# HIM-Otte-server-slow-control-V1-3.net
KiCad netlist of a schematic drawn in EAGLE
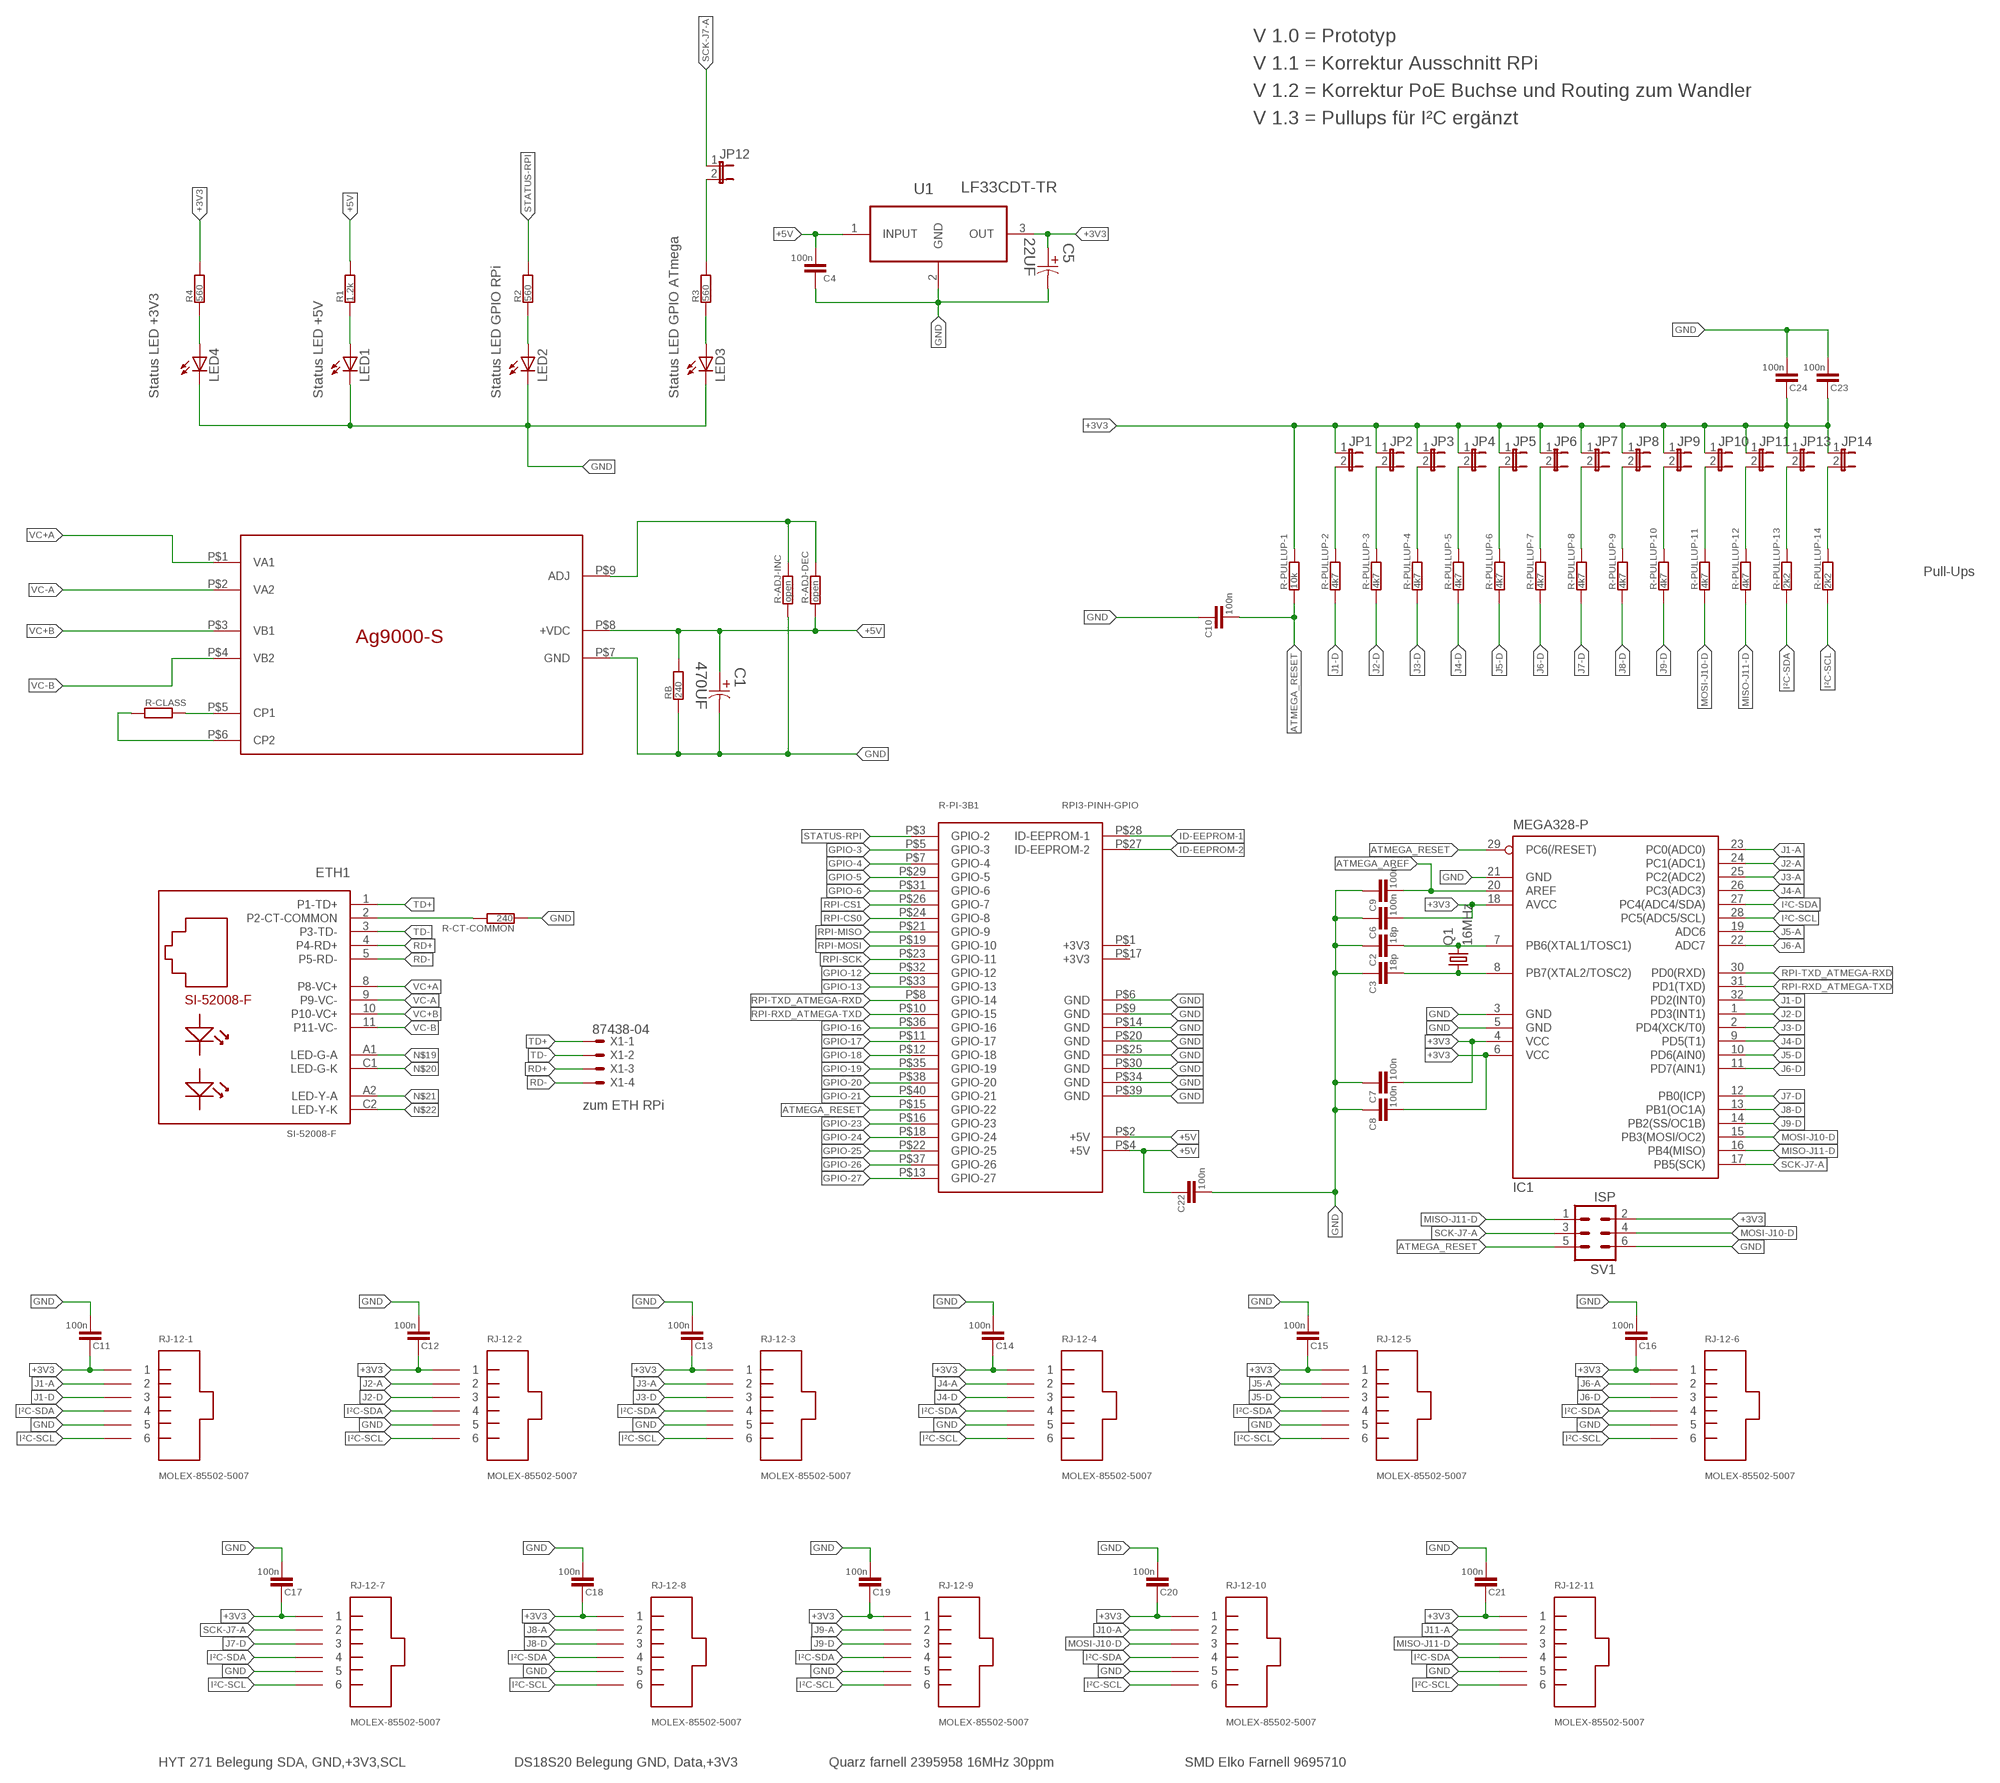
[diagram p0: schematic, sheet 1]

(export (version "E")
  (design (tool "Eeschema 10.0.6"))
  (components
    (comp (ref "C1")
      (value "470UF")
      (footprint "eagle-import:CAPAE830X1050N")
      (fields (field (name "MPN") "EEE-FK1C471P") (field (name "TOLERANCE") "±20 %"))
      (libsource (lib "eagle-import") (part "Panasonic-EEEFK_EEEFP_EEE--CASE-FFK1C471P"))
    )
    (comp (ref "C2")
      (value "18p")
      (footprint "eagle-import:C0603")
      (fields (field (name "TOLERANCE") "10%") (field (name "VOLTAGE") "16V"))
      (libsource (lib "eagle-import") (part "C-EUC0603"))
    )
    (comp (ref "C3")
      (value "18p")
      (footprint "eagle-import:C0603")
      (fields (field (name "TOLERANCE") "10%") (field (name "VOLTAGE") "16V"))
      (libsource (lib "eagle-import") (part "C-EUC0603"))
    )
    (comp (ref "C4")
      (value "100n")
      (footprint "eagle-import:C0603")
      (fields (field (name "TOLERANCE") "10%") (field (name "VOLTAGE") "16V"))
      (libsource (lib "eagle-import") (part "C-EUC0603"))
    )
    (comp (ref "C5")
      (value "22UF")
      (footprint "eagle-import:CAPAE530X610N")
      (fields (field (name "MPN") "EEE-FK1V220AR") (field (name "TOLERANCE") "±20 %"))
      (libsource (lib "eagle-import") (part "EEE--CASE-CFK1V220AR"))
    )
    (comp (ref "C6")
      (value "100n")
      (footprint "eagle-import:C0603")
      (fields (field (name "TOLERANCE") "10%") (field (name "VOLTAGE") "16V"))
      (libsource (lib "eagle-import") (part "C-EUC0603"))
    )
    (comp (ref "C7")
      (value "100n")
      (footprint "eagle-import:C0603")
      (fields (field (name "TOLERANCE") "10%") (field (name "VOLTAGE") "16V"))
      (libsource (lib "eagle-import") (part "C-EUC0603"))
    )
    (comp (ref "C8")
      (value "100n")
      (footprint "eagle-import:C0603")
      (fields (field (name "TOLERANCE") "10%") (field (name "VOLTAGE") "16V"))
      (libsource (lib "eagle-import") (part "C-EUC0603"))
    )
    (comp (ref "C9")
      (value "100n")
      (footprint "eagle-import:C0603")
      (fields (field (name "TOLERANCE") "10%") (field (name "VOLTAGE") "16V"))
      (libsource (lib "eagle-import") (part "C-EUC0603"))
    )
    (comp (ref "C10")
      (value "100n")
      (footprint "eagle-import:C0603")
      (fields (field (name "TOLERANCE") "10%") (field (name "VOLTAGE") "16V"))
      (libsource (lib "eagle-import") (part "C-EUC0603"))
    )
    (comp (ref "C11")
      (value "100n")
      (footprint "eagle-import:C0603")
      (fields (field (name "TOLERANCE") "10%") (field (name "VOLTAGE") "16V"))
      (libsource (lib "eagle-import") (part "C-EUC0603"))
    )
    (comp (ref "C12")
      (value "100n")
      (footprint "eagle-import:C0603")
      (fields (field (name "TOLERANCE") "10%") (field (name "VOLTAGE") "16V"))
      (libsource (lib "eagle-import") (part "C-EUC0603"))
    )
    (comp (ref "C13")
      (value "100n")
      (footprint "eagle-import:C0603")
      (fields (field (name "TOLERANCE") "10%") (field (name "VOLTAGE") "16V"))
      (libsource (lib "eagle-import") (part "C-EUC0603"))
    )
    (comp (ref "C14")
      (value "100n")
      (footprint "eagle-import:C0603")
      (fields (field (name "TOLERANCE") "10%") (field (name "VOLTAGE") "16V"))
      (libsource (lib "eagle-import") (part "C-EUC0603"))
    )
    (comp (ref "C15")
      (value "100n")
      (footprint "eagle-import:C0603")
      (fields (field (name "TOLERANCE") "10%") (field (name "VOLTAGE") "16V"))
      (libsource (lib "eagle-import") (part "C-EUC0603"))
    )
    (comp (ref "C16")
      (value "100n")
      (footprint "eagle-import:C0603")
      (fields (field (name "TOLERANCE") "10%") (field (name "VOLTAGE") "16V"))
      (libsource (lib "eagle-import") (part "C-EUC0603"))
    )
    (comp (ref "C17")
      (value "100n")
      (footprint "eagle-import:C0603")
      (fields (field (name "TOLERANCE") "10%") (field (name "VOLTAGE") "16V"))
      (libsource (lib "eagle-import") (part "C-EUC0603"))
    )
    (comp (ref "C18")
      (value "100n")
      (footprint "eagle-import:C0603")
      (fields (field (name "TOLERANCE") "10%") (field (name "VOLTAGE") "16V"))
      (libsource (lib "eagle-import") (part "C-EUC0603"))
    )
    (comp (ref "C19")
      (value "100n")
      (footprint "eagle-import:C0603")
      (fields (field (name "TOLERANCE") "10%") (field (name "VOLTAGE") "16V"))
      (libsource (lib "eagle-import") (part "C-EUC0603"))
    )
    (comp (ref "C20")
      (value "100n")
      (footprint "eagle-import:C0603")
      (fields (field (name "TOLERANCE") "10%") (field (name "VOLTAGE") "16V"))
      (libsource (lib "eagle-import") (part "C-EUC0603"))
    )
    (comp (ref "C21")
      (value "100n")
      (footprint "eagle-import:C0603")
      (fields (field (name "TOLERANCE") "10%") (field (name "VOLTAGE") "16V"))
      (libsource (lib "eagle-import") (part "C-EUC0603"))
    )
    (comp (ref "C22")
      (value "100n")
      (footprint "eagle-import:C0603")
      (fields (field (name "TOLERANCE") "10%") (field (name "VOLTAGE") "16V"))
      (libsource (lib "eagle-import") (part "C-EUC0603"))
    )
    (comp (ref "C23")
      (value "100n")
      (footprint "eagle-import:C0603")
      (fields (field (name "TOLERANCE") "10%") (field (name "VOLTAGE") "16V"))
      (libsource (lib "eagle-import") (part "C-EUC0603"))
    )
    (comp (ref "C24")
      (value "100n")
      (footprint "eagle-import:C0603")
      (fields (field (name "TOLERANCE") "10%") (field (name "VOLTAGE") "16V"))
      (libsource (lib "eagle-import") (part "C-EUC0603"))
    )
    (comp (ref "ETH1")
      (value "SI-52008-F")
      (footprint "eagle-import:SI-52008-F")
      (libsource (lib "eagle-import") (part "SI-52008-F"))
    )
    (comp (ref "IC1")
      (value "MEGA328-P")
      (footprint "eagle-import:TQFP32-08")
      (fields (field (name "MPN") "ATMEGA8-16AU"))
      (libsource (lib "eagle-import") (part "MEGA8-AI"))
    )
    (comp (ref "JP1")
      (value "JP1E")
      (footprint "eagle-import:JP1")
      (libsource (lib "eagle-import") (part "JP1E"))
    )
    (comp (ref "JP2")
      (value "JP1E")
      (footprint "eagle-import:JP1")
      (libsource (lib "eagle-import") (part "JP1E"))
    )
    (comp (ref "JP3")
      (value "JP1E")
      (footprint "eagle-import:JP1")
      (libsource (lib "eagle-import") (part "JP1E"))
    )
    (comp (ref "JP4")
      (value "JP1E")
      (footprint "eagle-import:JP1")
      (libsource (lib "eagle-import") (part "JP1E"))
    )
    (comp (ref "JP5")
      (value "JP1E")
      (footprint "eagle-import:JP1")
      (libsource (lib "eagle-import") (part "JP1E"))
    )
    (comp (ref "JP6")
      (value "JP1E")
      (footprint "eagle-import:JP1")
      (libsource (lib "eagle-import") (part "JP1E"))
    )
    (comp (ref "JP7")
      (value "JP1E")
      (footprint "eagle-import:JP1")
      (libsource (lib "eagle-import") (part "JP1E"))
    )
    (comp (ref "JP8")
      (value "JP1E")
      (footprint "eagle-import:JP1")
      (libsource (lib "eagle-import") (part "JP1E"))
    )
    (comp (ref "JP9")
      (value "JP1E")
      (footprint "eagle-import:JP1")
      (libsource (lib "eagle-import") (part "JP1E"))
    )
    (comp (ref "JP10")
      (value "JP1E")
      (footprint "eagle-import:JP1")
      (libsource (lib "eagle-import") (part "JP1E"))
    )
    (comp (ref "JP11")
      (value "JP1E")
      (footprint "eagle-import:JP1")
      (libsource (lib "eagle-import") (part "JP1E"))
    )
    (comp (ref "JP12")
      (value "JP1E")
      (footprint "eagle-import:JP1")
      (libsource (lib "eagle-import") (part "JP1E"))
    )
    (comp (ref "JP13")
      (value "JP1E")
      (footprint "eagle-import:JP1")
      (libsource (lib "eagle-import") (part "JP1E"))
    )
    (comp (ref "JP14")
      (value "JP1E")
      (footprint "eagle-import:JP1")
      (libsource (lib "eagle-import") (part "JP1E"))
    )
    (comp (ref "LED1")
      (value "LEDCHIPLED_0603")
      (footprint "eagle-import:CHIPLED_0603")
      (libsource (lib "eagle-import") (part "LEDCHIPLED_0603"))
    )
    (comp (ref "LED2")
      (value "LEDCHIPLED_0603")
      (footprint "eagle-import:CHIPLED_0603")
      (libsource (lib "eagle-import") (part "LEDCHIPLED_0603"))
    )
    (comp (ref "LED3")
      (value "LEDCHIPLED_0603")
      (footprint "eagle-import:CHIPLED_0603")
      (libsource (lib "eagle-import") (part "LEDCHIPLED_0603"))
    )
    (comp (ref "LED4")
      (value "LEDCHIPLED_0603")
      (footprint "eagle-import:CHIPLED_0603")
      (libsource (lib "eagle-import") (part "LEDCHIPLED_0603"))
    )
    (comp (ref "Q1")
      (value "16MHz")
      (footprint "eagle-import:HC49UP")
      (libsource (lib "eagle-import") (part "CRYSTALHC49UP"))
    )
    (comp (ref "R-ADJ-DEC")
      (value "open")
      (footprint "eagle-import:R0603")
      (fields (field (name "TOLERANCE") "1%"))
      (libsource (lib "eagle-import") (part "R-EU_R0603"))
    )
    (comp (ref "R-ADJ-INC")
      (value "open")
      (footprint "eagle-import:R0603")
      (fields (field (name "TOLERANCE") "1%"))
      (libsource (lib "eagle-import") (part "R-EU_R0603"))
    )
    (comp (ref "R-CLASS")
      (value "R-EU_R0603")
      (footprint "eagle-import:R0603")
      (fields (field (name "TOLERANCE") "1%"))
      (libsource (lib "eagle-import") (part "R-EU_R0603"))
    )
    (comp (ref "R-CT-COMMON")
      (value "240")
      (footprint "eagle-import:R0603")
      (fields (field (name "TOLERANCE") "1%"))
      (libsource (lib "eagle-import") (part "R-EU_R0603"))
    )
    (comp (ref "R-PI-3B1")
      (value "RPI3-PINH-GPIO")
      (footprint "eagle-import:RPI3-PINH-GPIO")
      (libsource (lib "eagle-import") (part "RPI3-PINH-GPIO"))
    )
    (comp (ref "R-PULLUP-1")
      (value "10k")
      (footprint "eagle-import:R0603")
      (fields (field (name "TOLERANCE") "1%"))
      (libsource (lib "eagle-import") (part "R-EU_R0603"))
    )
    (comp (ref "R-PULLUP-2")
      (value "4k7")
      (footprint "eagle-import:R0603")
      (fields (field (name "TOLERANCE") "1%"))
      (libsource (lib "eagle-import") (part "R-EU_R0603"))
    )
    (comp (ref "R-PULLUP-3")
      (value "4k7")
      (footprint "eagle-import:R0603")
      (fields (field (name "TOLERANCE") "1%"))
      (libsource (lib "eagle-import") (part "R-EU_R0603"))
    )
    (comp (ref "R-PULLUP-4")
      (value "4k7")
      (footprint "eagle-import:R0603")
      (fields (field (name "TOLERANCE") "1%"))
      (libsource (lib "eagle-import") (part "R-EU_R0603"))
    )
    (comp (ref "R-PULLUP-5")
      (value "4k7")
      (footprint "eagle-import:R0603")
      (fields (field (name "TOLERANCE") "1%"))
      (libsource (lib "eagle-import") (part "R-EU_R0603"))
    )
    (comp (ref "R-PULLUP-6")
      (value "4k7")
      (footprint "eagle-import:R0603")
      (fields (field (name "TOLERANCE") "1%"))
      (libsource (lib "eagle-import") (part "R-EU_R0603"))
    )
    (comp (ref "R-PULLUP-7")
      (value "4k7")
      (footprint "eagle-import:R0603")
      (fields (field (name "TOLERANCE") "1%"))
      (libsource (lib "eagle-import") (part "R-EU_R0603"))
    )
    (comp (ref "R-PULLUP-8")
      (value "4k7")
      (footprint "eagle-import:R0603")
      (fields (field (name "TOLERANCE") "1%"))
      (libsource (lib "eagle-import") (part "R-EU_R0603"))
    )
    (comp (ref "R-PULLUP-9")
      (value "4k7")
      (footprint "eagle-import:R0603")
      (fields (field (name "TOLERANCE") "1%"))
      (libsource (lib "eagle-import") (part "R-EU_R0603"))
    )
    (comp (ref "R-PULLUP-10")
      (value "4k7")
      (footprint "eagle-import:R0603")
      (fields (field (name "TOLERANCE") "1%"))
      (libsource (lib "eagle-import") (part "R-EU_R0603"))
    )
    (comp (ref "R-PULLUP-11")
      (value "4k7")
      (footprint "eagle-import:R0603")
      (fields (field (name "TOLERANCE") "1%"))
      (libsource (lib "eagle-import") (part "R-EU_R0603"))
    )
    (comp (ref "R-PULLUP-12")
      (value "4k7")
      (footprint "eagle-import:R0603")
      (fields (field (name "TOLERANCE") "1%"))
      (libsource (lib "eagle-import") (part "R-EU_R0603"))
    )
    (comp (ref "R-PULLUP-13")
      (value "2k2")
      (footprint "eagle-import:R0603")
      (fields (field (name "TOLERANCE") "1%"))
      (libsource (lib "eagle-import") (part "R-EU_R0603"))
    )
    (comp (ref "R-PULLUP-14")
      (value "2k2")
      (footprint "eagle-import:R0603")
      (fields (field (name "TOLERANCE") "1%"))
      (libsource (lib "eagle-import") (part "R-EU_R0603"))
    )
    (comp (ref "R1")
      (value "1.2k")
      (footprint "eagle-import:R0603")
      (fields (field (name "TOLERANCE") "1%"))
      (libsource (lib "eagle-import") (part "R-EU_R0603"))
    )
    (comp (ref "R2")
      (value "560")
      (footprint "eagle-import:R0603")
      (fields (field (name "TOLERANCE") "1%"))
      (libsource (lib "eagle-import") (part "R-EU_R0603"))
    )
    (comp (ref "R3")
      (value "560")
      (footprint "eagle-import:R0603")
      (fields (field (name "TOLERANCE") "1%"))
      (libsource (lib "eagle-import") (part "R-EU_R0603"))
    )
    (comp (ref "R4")
      (value "560")
      (footprint "eagle-import:R0603")
      (fields (field (name "TOLERANCE") "1%"))
      (libsource (lib "eagle-import") (part "R-EU_R0603"))
    )
    (comp (ref "RB")
      (value "240")
      (footprint "eagle-import:R0603")
      (fields (field (name "TOLERANCE") "1%"))
      (libsource (lib "eagle-import") (part "R-EU_R0603"))
    )
    (comp (ref "RJ-12-1")
      (value "MOLEX-85502-5007")
      (footprint "eagle-import:MOLEX-85502-5007")
      (libsource (lib "eagle-import") (part "MOLEX-85502-5007"))
    )
    (comp (ref "RJ-12-2")
      (value "MOLEX-85502-5007")
      (footprint "eagle-import:MOLEX-85502-5007")
      (libsource (lib "eagle-import") (part "MOLEX-85502-5007"))
    )
    (comp (ref "RJ-12-3")
      (value "MOLEX-85502-5007")
      (footprint "eagle-import:MOLEX-85502-5007")
      (libsource (lib "eagle-import") (part "MOLEX-85502-5007"))
    )
    (comp (ref "RJ-12-4")
      (value "MOLEX-85502-5007")
      (footprint "eagle-import:MOLEX-85502-5007")
      (libsource (lib "eagle-import") (part "MOLEX-85502-5007"))
    )
    (comp (ref "RJ-12-5")
      (value "MOLEX-85502-5007")
      (footprint "eagle-import:MOLEX-85502-5007")
      (libsource (lib "eagle-import") (part "MOLEX-85502-5007"))
    )
    (comp (ref "RJ-12-6")
      (value "MOLEX-85502-5007")
      (footprint "eagle-import:MOLEX-85502-5007")
      (libsource (lib "eagle-import") (part "MOLEX-85502-5007"))
    )
    (comp (ref "RJ-12-7")
      (value "MOLEX-85502-5007")
      (footprint "eagle-import:MOLEX-85502-5007")
      (libsource (lib "eagle-import") (part "MOLEX-85502-5007"))
    )
    (comp (ref "RJ-12-8")
      (value "MOLEX-85502-5007")
      (footprint "eagle-import:MOLEX-85502-5007")
      (libsource (lib "eagle-import") (part "MOLEX-85502-5007"))
    )
    (comp (ref "RJ-12-9")
      (value "MOLEX-85502-5007")
      (footprint "eagle-import:MOLEX-85502-5007")
      (libsource (lib "eagle-import") (part "MOLEX-85502-5007"))
    )
    (comp (ref "RJ-12-10")
      (value "MOLEX-85502-5007")
      (footprint "eagle-import:MOLEX-85502-5007")
      (libsource (lib "eagle-import") (part "MOLEX-85502-5007"))
    )
    (comp (ref "RJ-12-11")
      (value "MOLEX-85502-5007")
      (footprint "eagle-import:MOLEX-85502-5007")
      (libsource (lib "eagle-import") (part "MOLEX-85502-5007"))
    )
    (comp (ref "SV1")
      (value "ISP")
      (footprint "eagle-import:ML6")
      (libsource (lib "eagle-import") (part "ML6"))
    )
    (comp (ref "U$1")
      (value "AG9000-S")
      (footprint "eagle-import:AG9000-S")
      (libsource (lib "eagle-import") (part "AG9000-S"))
    )
    (comp (ref "U1")
      (value "LF33CDT-TR")
      (footprint "eagle-import:TO228P972X240-3N")
      (libsource (lib "eagle-import") (part "LF33CDT-TR"))
    )
    (comp (ref "X1")
      (value "87438-04")
      (footprint "eagle-import:87438-04")
      (libsource (lib "eagle-import") (part "87438-04"))
    )
  )
  (nets
    (net (code "1") (name "+3V3") (class "Default")
      (node (ref "C11") (pin "1") (pinfunction "1_1") (pintype "passive"))
      (node (ref "C12") (pin "1") (pinfunction "1_1") (pintype "passive"))
      (node (ref "C13") (pin "1") (pinfunction "1_1") (pintype "passive"))
      (node (ref "C14") (pin "1") (pinfunction "1_1") (pintype "passive"))
      (node (ref "C15") (pin "1") (pinfunction "1_1") (pintype "passive"))
      (node (ref "C16") (pin "1") (pinfunction "1_1") (pintype "passive"))
      (node (ref "C17") (pin "1") (pinfunction "1_1") (pintype "passive"))
      (node (ref "C18") (pin "1") (pinfunction "1_1") (pintype "passive"))
      (node (ref "C19") (pin "1") (pinfunction "1_1") (pintype "passive"))
      (node (ref "C20") (pin "1") (pinfunction "1_1") (pintype "passive"))
      (node (ref "C21") (pin "1") (pinfunction "1_1") (pintype "passive"))
      (node (ref "C23") (pin "1") (pinfunction "1_1") (pintype "passive"))
      (node (ref "C24") (pin "1") (pinfunction "1_1") (pintype "passive"))
      (node (ref "C5") (pin "1") (pinfunction "1_1") (pintype "passive"))
      (node (ref "C6") (pin "2") (pinfunction "2_2") (pintype "passive"))
      (node (ref "C7") (pin "2") (pinfunction "2_2") (pintype "passive"))
      (node (ref "C8") (pin "2") (pinfunction "2_2") (pintype "passive"))
      (node (ref "IC1") (pin "18") (pinfunction "AVCC_18") (pintype "power_in"))
      (node (ref "IC1") (pin "4") (pinfunction "VCC_4") (pintype "power_in"))
      (node (ref "IC1") (pin "6") (pinfunction "VCC_6") (pintype "power_in"))
      (node (ref "JP1") (pin "1") (pinfunction "1_1") (pintype "passive"))
      (node (ref "JP10") (pin "1") (pinfunction "1_1") (pintype "passive"))
      (node (ref "JP11") (pin "1") (pinfunction "1_1") (pintype "passive"))
      (node (ref "JP13") (pin "1") (pinfunction "1_1") (pintype "passive"))
      (node (ref "JP14") (pin "1") (pinfunction "1_1") (pintype "passive"))
      (node (ref "JP2") (pin "1") (pinfunction "1_1") (pintype "passive"))
      (node (ref "JP3") (pin "1") (pinfunction "1_1") (pintype "passive"))
      (node (ref "JP4") (pin "1") (pinfunction "1_1") (pintype "passive"))
      (node (ref "JP5") (pin "1") (pinfunction "1_1") (pintype "passive"))
      (node (ref "JP6") (pin "1") (pinfunction "1_1") (pintype "passive"))
      (node (ref "JP7") (pin "1") (pinfunction "1_1") (pintype "passive"))
      (node (ref "JP8") (pin "1") (pinfunction "1_1") (pintype "passive"))
      (node (ref "JP9") (pin "1") (pinfunction "1_1") (pintype "passive"))
      (node (ref "R-PULLUP-1") (pin "2") (pinfunction "2_2") (pintype "passive"))
      (node (ref "R4") (pin "2") (pinfunction "2_2") (pintype "passive"))
      (node (ref "RJ-12-1") (pin "1") (pinfunction "1_1") (pintype "bidirectional"))
      (node (ref "RJ-12-10") (pin "1") (pinfunction "1_1") (pintype "bidirectional"))
      (node (ref "RJ-12-11") (pin "1") (pinfunction "1_1") (pintype "bidirectional"))
      (node (ref "RJ-12-2") (pin "1") (pinfunction "1_1") (pintype "bidirectional"))
      (node (ref "RJ-12-3") (pin "1") (pinfunction "1_1") (pintype "bidirectional"))
      (node (ref "RJ-12-4") (pin "1") (pinfunction "1_1") (pintype "bidirectional"))
      (node (ref "RJ-12-5") (pin "1") (pinfunction "1_1") (pintype "bidirectional"))
      (node (ref "RJ-12-6") (pin "1") (pinfunction "1_1") (pintype "bidirectional"))
      (node (ref "RJ-12-7") (pin "1") (pinfunction "1_1") (pintype "bidirectional"))
      (node (ref "RJ-12-8") (pin "1") (pinfunction "1_1") (pintype "bidirectional"))
      (node (ref "RJ-12-9") (pin "1") (pinfunction "1_1") (pintype "bidirectional"))
      (node (ref "SV1") (pin "2") (pinfunction "2_2") (pintype "passive"))
      (node (ref "U1") (pin "3") (pinfunction "OUT_3") (pintype "output"))
    )
    (net (code "2") (name "+5V") (class "Default")
      (node (ref "C1") (pin "1") (pinfunction "1_1") (pintype "passive"))
      (node (ref "C22") (pin "1") (pinfunction "1_1") (pintype "passive"))
      (node (ref "C4") (pin "2") (pinfunction "2_2") (pintype "passive"))
      (node (ref "R-ADJ-DEC") (pin "1") (pinfunction "1_1") (pintype "passive"))
      (node (ref "R-PI-3B1") (pin "P$2") (pinfunction "+5V_P$2") (pintype "bidirectional"))
      (node (ref "R-PI-3B1") (pin "P$4") (pinfunction "+5V_P$4") (pintype "bidirectional"))
      (node (ref "R1") (pin "2") (pinfunction "2_2") (pintype "passive"))
      (node (ref "RB") (pin "2") (pinfunction "2_2") (pintype "passive"))
      (node (ref "U$1") (pin "P$8") (pinfunction "+VDC_P$8") (pintype "output"))
      (node (ref "U1") (pin "1") (pinfunction "INPUT_1") (pintype "input"))
    )
    (net (code "3") (name "ATMEGA_AREF") (class "Default")
      (node (ref "C9") (pin "2") (pinfunction "2_2") (pintype "passive"))
      (node (ref "IC1") (pin "20") (pinfunction "AREF_20") (pintype "passive"))
    )
    (net (code "4") (name "ATMEGA_RESET") (class "Default")
      (node (ref "C10") (pin "2") (pinfunction "2_2") (pintype "passive"))
      (node (ref "IC1") (pin "29") (pinfunction "PC6(/RESET)_29") (pintype "bidirectional"))
      (node (ref "R-PI-3B1") (pin "P$15") (pinfunction "GPIO-22_P$15") (pintype "bidirectional"))
      (node (ref "R-PULLUP-1") (pin "1") (pinfunction "1_1") (pintype "passive"))
      (node (ref "SV1") (pin "5") (pinfunction "5_5") (pintype "passive"))
    )
    (net (code "5") (name "GND") (class "Default")
      (node (ref "C1") (pin "2") (pinfunction "2_2") (pintype "passive"))
      (node (ref "C10") (pin "1") (pinfunction "1_1") (pintype "passive"))
      (node (ref "C11") (pin "2") (pinfunction "2_2") (pintype "passive"))
      (node (ref "C12") (pin "2") (pinfunction "2_2") (pintype "passive"))
      (node (ref "C13") (pin "2") (pinfunction "2_2") (pintype "passive"))
      (node (ref "C14") (pin "2") (pinfunction "2_2") (pintype "passive"))
      (node (ref "C15") (pin "2") (pinfunction "2_2") (pintype "passive"))
      (node (ref "C16") (pin "2") (pinfunction "2_2") (pintype "passive"))
      (node (ref "C17") (pin "2") (pinfunction "2_2") (pintype "passive"))
      (node (ref "C18") (pin "2") (pinfunction "2_2") (pintype "passive"))
      (node (ref "C19") (pin "2") (pinfunction "2_2") (pintype "passive"))
      (node (ref "C2") (pin "1") (pinfunction "1_1") (pintype "passive"))
      (node (ref "C20") (pin "2") (pinfunction "2_2") (pintype "passive"))
      (node (ref "C21") (pin "2") (pinfunction "2_2") (pintype "passive"))
      (node (ref "C22") (pin "2") (pinfunction "2_2") (pintype "passive"))
      (node (ref "C23") (pin "2") (pinfunction "2_2") (pintype "passive"))
      (node (ref "C24") (pin "2") (pinfunction "2_2") (pintype "passive"))
      (node (ref "C3") (pin "1") (pinfunction "1_1") (pintype "passive"))
      (node (ref "C4") (pin "1") (pinfunction "1_1") (pintype "passive"))
      (node (ref "C5") (pin "2") (pinfunction "2_2") (pintype "passive"))
      (node (ref "C6") (pin "1") (pinfunction "1_1") (pintype "passive"))
      (node (ref "C7") (pin "1") (pinfunction "1_1") (pintype "passive"))
      (node (ref "C8") (pin "1") (pinfunction "1_1") (pintype "passive"))
      (node (ref "C9") (pin "1") (pinfunction "1_1") (pintype "passive"))
      (node (ref "IC1") (pin "21") (pinfunction "GND_21") (pintype "power_in"))
      (node (ref "IC1") (pin "3") (pinfunction "GND_3") (pintype "power_in"))
      (node (ref "IC1") (pin "5") (pinfunction "GND_5") (pintype "power_in"))
      (node (ref "LED1") (pin "C") (pinfunction "C_C") (pintype "passive"))
      (node (ref "LED2") (pin "C") (pinfunction "C_C") (pintype "passive"))
      (node (ref "LED3") (pin "C") (pinfunction "C_C") (pintype "passive"))
      (node (ref "LED4") (pin "C") (pinfunction "C_C") (pintype "passive"))
      (node (ref "R-ADJ-INC") (pin "1") (pinfunction "1_1") (pintype "passive"))
      (node (ref "R-CT-COMMON") (pin "1") (pinfunction "1_1") (pintype "passive"))
      (node (ref "R-PI-3B1") (pin "P$14") (pinfunction "GND_P$14") (pintype "bidirectional"))
      (node (ref "R-PI-3B1") (pin "P$20") (pinfunction "GND_P$20") (pintype "bidirectional"))
      (node (ref "R-PI-3B1") (pin "P$25") (pinfunction "GND_P$25") (pintype "bidirectional"))
      (node (ref "R-PI-3B1") (pin "P$30") (pinfunction "GND_P$30") (pintype "bidirectional"))
      (node (ref "R-PI-3B1") (pin "P$34") (pinfunction "GND_P$34") (pintype "bidirectional"))
      (node (ref "R-PI-3B1") (pin "P$39") (pinfunction "GND_P$39") (pintype "bidirectional"))
      (node (ref "R-PI-3B1") (pin "P$6") (pinfunction "GND_P$6") (pintype "bidirectional"))
      (node (ref "R-PI-3B1") (pin "P$9") (pinfunction "GND_P$9") (pintype "bidirectional"))
      (node (ref "RB") (pin "1") (pinfunction "1_1") (pintype "passive"))
      (node (ref "RJ-12-1") (pin "5") (pinfunction "5_5") (pintype "bidirectional"))
      (node (ref "RJ-12-10") (pin "5") (pinfunction "5_5") (pintype "bidirectional"))
      (node (ref "RJ-12-11") (pin "5") (pinfunction "5_5") (pintype "bidirectional"))
      (node (ref "RJ-12-2") (pin "5") (pinfunction "5_5") (pintype "bidirectional"))
      (node (ref "RJ-12-3") (pin "5") (pinfunction "5_5") (pintype "bidirectional"))
      (node (ref "RJ-12-4") (pin "5") (pinfunction "5_5") (pintype "bidirectional"))
      (node (ref "RJ-12-5") (pin "5") (pinfunction "5_5") (pintype "bidirectional"))
      (node (ref "RJ-12-6") (pin "5") (pinfunction "5_5") (pintype "bidirectional"))
      (node (ref "RJ-12-7") (pin "5") (pinfunction "5_5") (pintype "bidirectional"))
      (node (ref "RJ-12-8") (pin "5") (pinfunction "5_5") (pintype "bidirectional"))
      (node (ref "RJ-12-9") (pin "5") (pinfunction "5_5") (pintype "bidirectional"))
      (node (ref "SV1") (pin "6") (pinfunction "6_6") (pintype "passive"))
      (node (ref "U$1") (pin "P$7") (pinfunction "GND_P$7") (pintype "output"))
      (node (ref "U1") (pin "2") (pinfunction "GND_2") (pintype "passive"))
    )
    (net (code "6") (name "GPIO-3") (class "Default")
      (node (ref "R-PI-3B1") (pin "P$5") (pinfunction "GPIO-3_P$5") (pintype "bidirectional"))
    )
    (net (code "7") (name "GPIO-4") (class "Default")
      (node (ref "R-PI-3B1") (pin "P$7") (pinfunction "GPIO-4_P$7") (pintype "bidirectional"))
    )
    (net (code "8") (name "GPIO-5") (class "Default")
      (node (ref "R-PI-3B1") (pin "P$29") (pinfunction "GPIO-5_P$29") (pintype "bidirectional"))
    )
    (net (code "9") (name "GPIO-6") (class "Default")
      (node (ref "R-PI-3B1") (pin "P$31") (pinfunction "GPIO-6_P$31") (pintype "bidirectional"))
    )
    (net (code "10") (name "GPIO-12") (class "Default")
      (node (ref "R-PI-3B1") (pin "P$32") (pinfunction "GPIO-12_P$32") (pintype "bidirectional"))
    )
    (net (code "11") (name "GPIO-13") (class "Default")
      (node (ref "R-PI-3B1") (pin "P$33") (pinfunction "GPIO-13_P$33") (pintype "bidirectional"))
    )
    (net (code "12") (name "GPIO-16") (class "Default")
      (node (ref "R-PI-3B1") (pin "P$36") (pinfunction "GPIO-16_P$36") (pintype "bidirectional"))
    )
    (net (code "13") (name "GPIO-17") (class "Default")
      (node (ref "R-PI-3B1") (pin "P$11") (pinfunction "GPIO-17_P$11") (pintype "bidirectional"))
    )
    (net (code "14") (name "GPIO-18") (class "Default")
      (node (ref "R-PI-3B1") (pin "P$12") (pinfunction "GPIO-18_P$12") (pintype "bidirectional"))
    )
    (net (code "15") (name "GPIO-19") (class "Default")
      (node (ref "R-PI-3B1") (pin "P$35") (pinfunction "GPIO-19_P$35") (pintype "bidirectional"))
    )
    (net (code "16") (name "GPIO-20") (class "Default")
      (node (ref "R-PI-3B1") (pin "P$38") (pinfunction "GPIO-20_P$38") (pintype "bidirectional"))
    )
    (net (code "17") (name "GPIO-21") (class "Default")
      (node (ref "R-PI-3B1") (pin "P$40") (pinfunction "GPIO-21_P$40") (pintype "bidirectional"))
    )
    (net (code "18") (name "GPIO-23") (class "Default")
      (node (ref "R-PI-3B1") (pin "P$16") (pinfunction "GPIO-23_P$16") (pintype "bidirectional"))
    )
    (net (code "19") (name "GPIO-24") (class "Default")
      (node (ref "R-PI-3B1") (pin "P$18") (pinfunction "GPIO-24_P$18") (pintype "bidirectional"))
    )
    (net (code "20") (name "GPIO-25") (class "Default")
      (node (ref "R-PI-3B1") (pin "P$22") (pinfunction "GPIO-25_P$22") (pintype "bidirectional"))
    )
    (net (code "21") (name "GPIO-26") (class "Default")
      (node (ref "R-PI-3B1") (pin "P$37") (pinfunction "GPIO-26_P$37") (pintype "bidirectional"))
    )
    (net (code "22") (name "GPIO-27") (class "Default")
      (node (ref "R-PI-3B1") (pin "P$13") (pinfunction "GPIO-27_P$13") (pintype "bidirectional"))
    )
    (net (code "23") (name "ID-EEPROM-1") (class "Default")
      (node (ref "R-PI-3B1") (pin "P$28") (pinfunction "ID-EEPROM-1_P$28") (pintype "bidirectional"))
    )
    (net (code "24") (name "ID-EEPROM-2") (class "Default")
      (node (ref "R-PI-3B1") (pin "P$27") (pinfunction "ID-EEPROM-2_P$27") (pintype "bidirectional"))
    )
    (net (code "25") (name "I²C-SCL") (class "Default")
      (node (ref "IC1") (pin "28") (pinfunction "PC5(ADC5/SCL)_28") (pintype "bidirectional"))
      (node (ref "R-PULLUP-14") (pin "1") (pinfunction "1_1") (pintype "passive"))
      (node (ref "RJ-12-1") (pin "6") (pinfunction "6_6") (pintype "bidirectional"))
      (node (ref "RJ-12-10") (pin "6") (pinfunction "6_6") (pintype "bidirectional"))
      (node (ref "RJ-12-11") (pin "6") (pinfunction "6_6") (pintype "bidirectional"))
      (node (ref "RJ-12-2") (pin "6") (pinfunction "6_6") (pintype "bidirectional"))
      (node (ref "RJ-12-3") (pin "6") (pinfunction "6_6") (pintype "bidirectional"))
      (node (ref "RJ-12-4") (pin "6") (pinfunction "6_6") (pintype "bidirectional"))
      (node (ref "RJ-12-5") (pin "6") (pinfunction "6_6") (pintype "bidirectional"))
      (node (ref "RJ-12-6") (pin "6") (pinfunction "6_6") (pintype "bidirectional"))
      (node (ref "RJ-12-7") (pin "6") (pinfunction "6_6") (pintype "bidirectional"))
      (node (ref "RJ-12-8") (pin "6") (pinfunction "6_6") (pintype "bidirectional"))
      (node (ref "RJ-12-9") (pin "6") (pinfunction "6_6") (pintype "bidirectional"))
    )
    (net (code "26") (name "I²C-SDA") (class "Default")
      (node (ref "IC1") (pin "27") (pinfunction "PC4(ADC4/SDA)_27") (pintype "bidirectional"))
      (node (ref "R-PULLUP-13") (pin "1") (pinfunction "1_1") (pintype "passive"))
      (node (ref "RJ-12-1") (pin "4") (pinfunction "4_4") (pintype "bidirectional"))
      (node (ref "RJ-12-10") (pin "4") (pinfunction "4_4") (pintype "bidirectional"))
      (node (ref "RJ-12-11") (pin "4") (pinfunction "4_4") (pintype "bidirectional"))
      (node (ref "RJ-12-2") (pin "4") (pinfunction "4_4") (pintype "bidirectional"))
      (node (ref "RJ-12-3") (pin "4") (pinfunction "4_4") (pintype "bidirectional"))
      (node (ref "RJ-12-4") (pin "4") (pinfunction "4_4") (pintype "bidirectional"))
      (node (ref "RJ-12-5") (pin "4") (pinfunction "4_4") (pintype "bidirectional"))
      (node (ref "RJ-12-6") (pin "4") (pinfunction "4_4") (pintype "bidirectional"))
      (node (ref "RJ-12-7") (pin "4") (pinfunction "4_4") (pintype "bidirectional"))
      (node (ref "RJ-12-8") (pin "4") (pinfunction "4_4") (pintype "bidirectional"))
      (node (ref "RJ-12-9") (pin "4") (pinfunction "4_4") (pintype "bidirectional"))
    )
    (net (code "27") (name "J1-A") (class "Default")
      (node (ref "IC1") (pin "23") (pinfunction "PC0(ADC0)_23") (pintype "bidirectional"))
      (node (ref "RJ-12-1") (pin "2") (pinfunction "2_2") (pintype "bidirectional"))
    )
    (net (code "28") (name "J1-D") (class "Default")
      (node (ref "IC1") (pin "32") (pinfunction "PD2(INT0)_32") (pintype "bidirectional"))
      (node (ref "R-PULLUP-2") (pin "1") (pinfunction "1_1") (pintype "passive"))
      (node (ref "RJ-12-1") (pin "3") (pinfunction "3_3") (pintype "bidirectional"))
    )
    (net (code "29") (name "J2-A") (class "Default")
      (node (ref "IC1") (pin "24") (pinfunction "PC1(ADC1)_24") (pintype "bidirectional"))
      (node (ref "RJ-12-2") (pin "2") (pinfunction "2_2") (pintype "bidirectional"))
    )
    (net (code "30") (name "J2-D") (class "Default")
      (node (ref "IC1") (pin "1") (pinfunction "PD3(INT1)_1") (pintype "bidirectional"))
      (node (ref "R-PULLUP-3") (pin "1") (pinfunction "1_1") (pintype "passive"))
      (node (ref "RJ-12-2") (pin "3") (pinfunction "3_3") (pintype "bidirectional"))
    )
    (net (code "31") (name "J3-A") (class "Default")
      (node (ref "IC1") (pin "25") (pinfunction "PC2(ADC2)_25") (pintype "bidirectional"))
      (node (ref "RJ-12-3") (pin "2") (pinfunction "2_2") (pintype "bidirectional"))
    )
    (net (code "32") (name "J3-D") (class "Default")
      (node (ref "IC1") (pin "2") (pinfunction "PD4(XCK/T0)_2") (pintype "bidirectional"))
      (node (ref "R-PULLUP-4") (pin "1") (pinfunction "1_1") (pintype "passive"))
      (node (ref "RJ-12-3") (pin "3") (pinfunction "3_3") (pintype "bidirectional"))
    )
    (net (code "33") (name "J4-A") (class "Default")
      (node (ref "IC1") (pin "26") (pinfunction "PC3(ADC3)_26") (pintype "bidirectional"))
      (node (ref "RJ-12-4") (pin "2") (pinfunction "2_2") (pintype "bidirectional"))
    )
    (net (code "34") (name "J4-D") (class "Default")
      (node (ref "IC1") (pin "9") (pinfunction "PD5(T1)_9") (pintype "bidirectional"))
      (node (ref "R-PULLUP-5") (pin "1") (pinfunction "1_1") (pintype "passive"))
      (node (ref "RJ-12-4") (pin "3") (pinfunction "3_3") (pintype "bidirectional"))
    )
    (net (code "35") (name "J5-A") (class "Default")
      (node (ref "IC1") (pin "19") (pinfunction "ADC6_19") (pintype "bidirectional"))
      (node (ref "RJ-12-5") (pin "2") (pinfunction "2_2") (pintype "bidirectional"))
    )
    (net (code "36") (name "J5-D") (class "Default")
      (node (ref "IC1") (pin "10") (pinfunction "PD6(AIN0)_10") (pintype "bidirectional"))
      (node (ref "R-PULLUP-6") (pin "1") (pinfunction "1_1") (pintype "passive"))
      (node (ref "RJ-12-5") (pin "3") (pinfunction "3_3") (pintype "bidirectional"))
    )
    (net (code "37") (name "J6-A") (class "Default")
      (node (ref "IC1") (pin "22") (pinfunction "ADC7_22") (pintype "bidirectional"))
      (node (ref "RJ-12-6") (pin "2") (pinfunction "2_2") (pintype "bidirectional"))
    )
    (net (code "38") (name "J6-D") (class "Default")
      (node (ref "IC1") (pin "11") (pinfunction "PD7(AIN1)_11") (pintype "bidirectional"))
      (node (ref "R-PULLUP-7") (pin "1") (pinfunction "1_1") (pintype "passive"))
      (node (ref "RJ-12-6") (pin "3") (pinfunction "3_3") (pintype "bidirectional"))
    )
    (net (code "39") (name "J7-D") (class "Default")
      (node (ref "IC1") (pin "12") (pinfunction "PB0(ICP)_12") (pintype "bidirectional"))
      (node (ref "R-PULLUP-8") (pin "1") (pinfunction "1_1") (pintype "passive"))
      (node (ref "RJ-12-7") (pin "3") (pinfunction "3_3") (pintype "bidirectional"))
    )
    (net (code "40") (name "J8-A") (class "Default")
      (node (ref "RJ-12-8") (pin "2") (pinfunction "2_2") (pintype "bidirectional"))
    )
    (net (code "41") (name "J8-D") (class "Default")
      (node (ref "IC1") (pin "13") (pinfunction "PB1(OC1A)_13") (pintype "bidirectional"))
      (node (ref "R-PULLUP-9") (pin "1") (pinfunction "1_1") (pintype "passive"))
      (node (ref "RJ-12-8") (pin "3") (pinfunction "3_3") (pintype "bidirectional"))
    )
    (net (code "42") (name "J9-A") (class "Default")
      (node (ref "RJ-12-9") (pin "2") (pinfunction "2_2") (pintype "bidirectional"))
    )
    (net (code "43") (name "J9-D") (class "Default")
      (node (ref "IC1") (pin "14") (pinfunction "PB2(SS/OC1B)_14") (pintype "bidirectional"))
      (node (ref "R-PULLUP-10") (pin "1") (pinfunction "1_1") (pintype "passive"))
      (node (ref "RJ-12-9") (pin "3") (pinfunction "3_3") (pintype "bidirectional"))
    )
    (net (code "44") (name "J10-A") (class "Default")
      (node (ref "RJ-12-10") (pin "2") (pinfunction "2_2") (pintype "bidirectional"))
    )
    (net (code "45") (name "J11-A") (class "Default")
      (node (ref "RJ-12-11") (pin "2") (pinfunction "2_2") (pintype "bidirectional"))
    )
    (net (code "46") (name "MISO-J11-D") (class "Default")
      (node (ref "IC1") (pin "16") (pinfunction "PB4(MISO)_16") (pintype "bidirectional"))
      (node (ref "R-PULLUP-12") (pin "1") (pinfunction "1_1") (pintype "passive"))
      (node (ref "RJ-12-11") (pin "3") (pinfunction "3_3") (pintype "bidirectional"))
      (node (ref "SV1") (pin "1") (pinfunction "1_1") (pintype "passive"))
    )
    (net (code "47") (name "MOSI-J10-D") (class "Default")
      (node (ref "IC1") (pin "15") (pinfunction "PB3(MOSI/OC2)_15") (pintype "bidirectional"))
      (node (ref "R-PULLUP-11") (pin "1") (pinfunction "1_1") (pintype "passive"))
      (node (ref "RJ-12-10") (pin "3") (pinfunction "3_3") (pintype "bidirectional"))
      (node (ref "SV1") (pin "4") (pinfunction "4_4") (pintype "passive"))
    )
    (net (code "48") (name "N$19") (class "Default")
      (node (ref "ETH1") (pin "A1") (pinfunction "LED-G-A_A1") (pintype "bidirectional"))
    )
    (net (code "49") (name "N$20") (class "Default")
      (node (ref "ETH1") (pin "C1") (pinfunction "LED-G-K_C1") (pintype "bidirectional"))
    )
    (net (code "50") (name "N$21") (class "Default")
      (node (ref "ETH1") (pin "A2") (pinfunction "LED-Y-A_A2") (pintype "bidirectional"))
    )
    (net (code "51") (name "N$22") (class "Default")
      (node (ref "ETH1") (pin "C2") (pinfunction "LED-Y-K_C2") (pintype "bidirectional"))
    )
    (net (code "52") (name "Net-(ETH1-P2-CT-COMMON)") (class "Default")
      (node (ref "ETH1") (pin "2") (pinfunction "P2-CT-COMMON_2") (pintype "bidirectional"))
      (node (ref "R-CT-COMMON") (pin "2") (pinfunction "2_2") (pintype "passive"))
    )
    (net (code "53") (name "Net-(IC1-PB6(XTAL1{slash}TOSC1))") (class "Default")
      (node (ref "C2") (pin "2") (pinfunction "2_2") (pintype "passive"))
      (node (ref "IC1") (pin "7") (pinfunction "PB6(XTAL1/TOSC1)_7") (pintype "bidirectional"))
      (node (ref "Q1") (pin "2") (pinfunction "2_2") (pintype "passive"))
    )
    (net (code "54") (name "Net-(IC1-PB7(XTAL2{slash}TOSC2))") (class "Default")
      (node (ref "C3") (pin "2") (pinfunction "2_2") (pintype "passive"))
      (node (ref "IC1") (pin "8") (pinfunction "PB7(XTAL2/TOSC2)_8") (pintype "bidirectional"))
      (node (ref "Q1") (pin "1") (pinfunction "1_1") (pintype "passive"))
    )
    (net (code "55") (name "Net-(JP1-Pad2)") (class "Default")
      (node (ref "JP1") (pin "2") (pinfunction "2_2") (pintype "passive"))
      (node (ref "R-PULLUP-2") (pin "2") (pinfunction "2_2") (pintype "passive"))
    )
    (net (code "56") (name "Net-(JP2-Pad2)") (class "Default")
      (node (ref "JP2") (pin "2") (pinfunction "2_2") (pintype "passive"))
      (node (ref "R-PULLUP-3") (pin "2") (pinfunction "2_2") (pintype "passive"))
    )
    (net (code "57") (name "Net-(JP3-Pad2)") (class "Default")
      (node (ref "JP3") (pin "2") (pinfunction "2_2") (pintype "passive"))
      (node (ref "R-PULLUP-4") (pin "2") (pinfunction "2_2") (pintype "passive"))
    )
    (net (code "58") (name "Net-(JP4-Pad2)") (class "Default")
      (node (ref "JP4") (pin "2") (pinfunction "2_2") (pintype "passive"))
      (node (ref "R-PULLUP-5") (pin "2") (pinfunction "2_2") (pintype "passive"))
    )
    (net (code "59") (name "Net-(JP5-Pad2)") (class "Default")
      (node (ref "JP5") (pin "2") (pinfunction "2_2") (pintype "passive"))
      (node (ref "R-PULLUP-6") (pin "2") (pinfunction "2_2") (pintype "passive"))
    )
    (net (code "60") (name "Net-(JP6-Pad2)") (class "Default")
      (node (ref "JP6") (pin "2") (pinfunction "2_2") (pintype "passive"))
      (node (ref "R-PULLUP-7") (pin "2") (pinfunction "2_2") (pintype "passive"))
    )
    (net (code "61") (name "Net-(JP7-Pad2)") (class "Default")
      (node (ref "JP7") (pin "2") (pinfunction "2_2") (pintype "passive"))
      (node (ref "R-PULLUP-8") (pin "2") (pinfunction "2_2") (pintype "passive"))
    )
    (net (code "62") (name "Net-(JP8-Pad2)") (class "Default")
      (node (ref "JP8") (pin "2") (pinfunction "2_2") (pintype "passive"))
      (node (ref "R-PULLUP-9") (pin "2") (pinfunction "2_2") (pintype "passive"))
    )
    (net (code "63") (name "Net-(JP9-Pad2)") (class "Default")
      (node (ref "JP9") (pin "2") (pinfunction "2_2") (pintype "passive"))
      (node (ref "R-PULLUP-10") (pin "2") (pinfunction "2_2") (pintype "passive"))
    )
    (net (code "64") (name "Net-(JP10-Pad2)") (class "Default")
      (node (ref "JP10") (pin "2") (pinfunction "2_2") (pintype "passive"))
      (node (ref "R-PULLUP-11") (pin "2") (pinfunction "2_2") (pintype "passive"))
    )
    (net (code "65") (name "Net-(JP11-Pad2)") (class "Default")
      (node (ref "JP11") (pin "2") (pinfunction "2_2") (pintype "passive"))
      (node (ref "R-PULLUP-12") (pin "2") (pinfunction "2_2") (pintype "passive"))
    )
    (net (code "66") (name "Net-(JP12-Pad2)") (class "Default")
      (node (ref "JP12") (pin "2") (pinfunction "2_2") (pintype "passive"))
      (node (ref "R3") (pin "2") (pinfunction "2_2") (pintype "passive"))
    )
    (net (code "67") (name "Net-(JP13-Pad2)") (class "Default")
      (node (ref "JP13") (pin "2") (pinfunction "2_2") (pintype "passive"))
      (node (ref "R-PULLUP-13") (pin "2") (pinfunction "2_2") (pintype "passive"))
    )
    (net (code "68") (name "Net-(JP14-Pad2)") (class "Default")
      (node (ref "JP14") (pin "2") (pinfunction "2_2") (pintype "passive"))
      (node (ref "R-PULLUP-14") (pin "2") (pinfunction "2_2") (pintype "passive"))
    )
    (net (code "69") (name "Net-(LED1-PadA)") (class "Default")
      (node (ref "LED1") (pin "A") (pinfunction "A_A") (pintype "passive"))
      (node (ref "R1") (pin "1") (pinfunction "1_1") (pintype "passive"))
    )
    (net (code "70") (name "Net-(LED2-PadA)") (class "Default")
      (node (ref "LED2") (pin "A") (pinfunction "A_A") (pintype "passive"))
      (node (ref "R2") (pin "1") (pinfunction "1_1") (pintype "passive"))
    )
    (net (code "71") (name "Net-(LED3-PadA)") (class "Default")
      (node (ref "LED3") (pin "A") (pinfunction "A_A") (pintype "passive"))
      (node (ref "R3") (pin "1") (pinfunction "1_1") (pintype "passive"))
    )
    (net (code "72") (name "Net-(LED4-PadA)") (class "Default")
      (node (ref "LED4") (pin "A") (pinfunction "A_A") (pintype "passive"))
      (node (ref "R4") (pin "1") (pinfunction "1_1") (pintype "passive"))
    )
    (net (code "73") (name "Net-(U$1-ADJ)") (class "Default")
      (node (ref "R-ADJ-DEC") (pin "2") (pinfunction "2_2") (pintype "passive"))
      (node (ref "R-ADJ-INC") (pin "2") (pinfunction "2_2") (pintype "passive"))
      (node (ref "U$1") (pin "P$9") (pinfunction "ADJ_P$9") (pintype "bidirectional"))
    )
    (net (code "74") (name "Net-(U$1-CP1)") (class "Default")
      (node (ref "R-CLASS") (pin "2") (pinfunction "2_2") (pintype "passive"))
      (node (ref "U$1") (pin "P$5") (pinfunction "CP1_P$5") (pintype "bidirectional"))
    )
    (net (code "75") (name "Net-(U$1-CP2)") (class "Default")
      (node (ref "R-CLASS") (pin "1") (pinfunction "1_1") (pintype "passive"))
      (node (ref "U$1") (pin "P$6") (pinfunction "CP2_P$6") (pintype "bidirectional"))
    )
    (net (code "76") (name "RD+") (class "Default")
      (node (ref "ETH1") (pin "4") (pinfunction "P4-RD+_4") (pintype "bidirectional"))
      (node (ref "X1") (pin "3") (pinfunction "S_3") (pintype "passive"))
    )
    (net (code "77") (name "RD-") (class "Default")
      (node (ref "ETH1") (pin "5") (pinfunction "P5-RD-_5") (pintype "bidirectional"))
      (node (ref "X1") (pin "4") (pinfunction "S_4") (pintype "passive"))
    )
    (net (code "78") (name "RPI-CS0") (class "Default")
      (node (ref "R-PI-3B1") (pin "P$24") (pinfunction "GPIO-8_P$24") (pintype "bidirectional"))
    )
    (net (code "79") (name "RPI-CS1") (class "Default")
      (node (ref "R-PI-3B1") (pin "P$26") (pinfunction "GPIO-7_P$26") (pintype "bidirectional"))
    )
    (net (code "80") (name "RPI-MISO") (class "Default")
      (node (ref "R-PI-3B1") (pin "P$21") (pinfunction "GPIO-9_P$21") (pintype "bidirectional"))
    )
    (net (code "81") (name "RPI-MOSI") (class "Default")
      (node (ref "R-PI-3B1") (pin "P$19") (pinfunction "GPIO-10_P$19") (pintype "bidirectional"))
    )
    (net (code "82") (name "RPI-RXD_ATMEGA-TXD") (class "Default")
      (node (ref "IC1") (pin "31") (pinfunction "PD1(TXD)_31") (pintype "bidirectional"))
      (node (ref "R-PI-3B1") (pin "P$10") (pinfunction "GPIO-15_P$10") (pintype "bidirectional"))
    )
    (net (code "83") (name "RPI-SCK") (class "Default")
      (node (ref "R-PI-3B1") (pin "P$23") (pinfunction "GPIO-11_P$23") (pintype "bidirectional"))
    )
    (net (code "84") (name "RPI-TXD_ATMEGA-RXD") (class "Default")
      (node (ref "IC1") (pin "30") (pinfunction "PD0(RXD)_30") (pintype "bidirectional"))
      (node (ref "R-PI-3B1") (pin "P$8") (pinfunction "GPIO-14_P$8") (pintype "bidirectional"))
    )
    (net (code "85") (name "SCK-J7-A") (class "Default")
      (node (ref "IC1") (pin "17") (pinfunction "PB5(SCK)_17") (pintype "bidirectional"))
      (node (ref "JP12") (pin "1") (pinfunction "1_1") (pintype "passive"))
      (node (ref "RJ-12-7") (pin "2") (pinfunction "2_2") (pintype "bidirectional"))
      (node (ref "SV1") (pin "3") (pinfunction "3_3") (pintype "passive"))
    )
    (net (code "86") (name "STATUS-RPI") (class "Default")
      (node (ref "R-PI-3B1") (pin "P$3") (pinfunction "GPIO-2_P$3") (pintype "bidirectional"))
      (node (ref "R2") (pin "2") (pinfunction "2_2") (pintype "passive"))
    )
    (net (code "87") (name "TD+") (class "Default")
      (node (ref "ETH1") (pin "1") (pinfunction "P1-TD+_1") (pintype "bidirectional"))
      (node (ref "X1") (pin "1") (pinfunction "S_1") (pintype "passive"))
    )
    (net (code "88") (name "TD-") (class "Default")
      (node (ref "ETH1") (pin "3") (pinfunction "P3-TD-_3") (pintype "bidirectional"))
      (node (ref "X1") (pin "2") (pinfunction "S_2") (pintype "passive"))
    )
    (net (code "89") (name "VC+A") (class "Default")
      (node (ref "ETH1") (pin "8") (pinfunction "P8-VC+_8") (pintype "bidirectional"))
      (node (ref "U$1") (pin "P$1") (pinfunction "VA1_P$1") (pintype "input"))
    )
    (net (code "90") (name "VC+B") (class "Default")
      (node (ref "ETH1") (pin "10") (pinfunction "P10-VC+_10") (pintype "bidirectional"))
      (node (ref "U$1") (pin "P$3") (pinfunction "VB1_P$3") (pintype "input"))
    )
    (net (code "91") (name "VC-A") (class "Default")
      (node (ref "ETH1") (pin "9") (pinfunction "P9-VC-_9") (pintype "bidirectional"))
      (node (ref "U$1") (pin "P$2") (pinfunction "VA2_P$2") (pintype "input"))
    )
    (net (code "92") (name "VC-B") (class "Default")
      (node (ref "ETH1") (pin "11") (pinfunction "P11-VC-_11") (pintype "bidirectional"))
      (node (ref "U$1") (pin "P$4") (pinfunction "VB2_P$4") (pintype "input"))
    )
    (net (code "93") (name "unconnected-(R-PI-3B1-+3V3-PadP$1)") (class "Default")
      (node (ref "R-PI-3B1") (pin "P$1") (pinfunction "+3V3_P$1") (pintype "bidirectional"))
    )
    (net (code "94") (name "unconnected-(R-PI-3B1-+3V3-PadP$17)") (class "Default")
      (node (ref "R-PI-3B1") (pin "P$17") (pinfunction "+3V3_P$17") (pintype "bidirectional"))
    )
  )
)
